# 02_POWER.net
KiCad netlist of a schematic drawn in Altium Designer
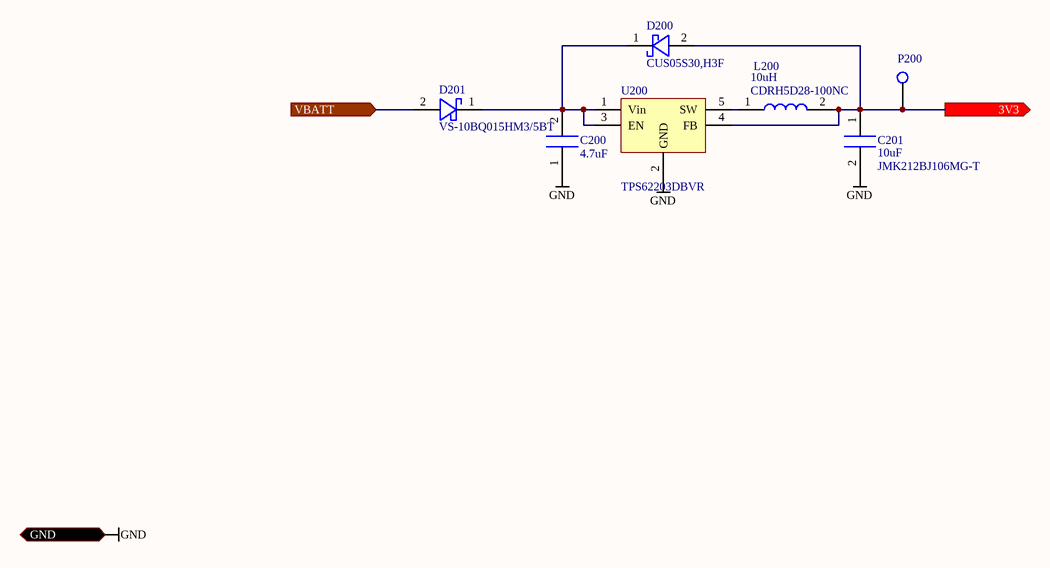
[diagram p0: 02_POWER.SchDoc]

(export (version "E")
  (design (tool "Eeschema 10.0.6"))
  (components
    (comp (ref "C200")
      (value "4.7uF")
      (footprint "CAP_0805")
      (description "CAP 4.7uF 10% 106 0805 X7R")
      (fields (field (name "TOLERANCE") "10%") (field (name "MANUFACTURER") "MURATA"))
      (libsource (lib "Capacitors") (part "4.7uF_10%_16V_0805_X7R_GRM21BR71C475KE51L"))
    )
    (comp (ref "C201")
      (value "10uF")
      (footprint "CAP_0805")
      (description "CAP 10uF 20% 6.3V 0805 X5R")
      (fields
        (field (name "TOLERANCE") "20%")
        (field (name "MANUFACTURER") "TAYIO YUDEN")
        (field (name "MANUFACTURER REFERENCE") "JMK212BJ106MG-T")
      )
      (libsource (lib "Capacitors") (part "10uF_20%_6.3V_0805_X5R_JMK212BJ106MG-T"))
    )
    (comp (ref "D200")
      (value "DIODE_30V_500mA_340mVf_CUS05S30,H3F")
      (footprint "SOD-323")
      (description "DIODE 30V 500mA 340mVf CUS05S30,H3F")
      (fields (field (name "MANUFACTURER") "TOSHIBA") (field (name "MANUFACTURER REFERENCE") "CUS05S30,H3F"))
      (libsource (lib "Semiconductor") (part "DIODE_30V_500mA_340mVf_CUS05S30,H3F"))
    )
    (comp (ref "D201")
      (value "DIODE_15V_1A_210mVf_VS-10BQ015HM3/5BT")
      (description "DIODE 15V 1A 210mVf VS-10BQ015HM3/5BT")
      (fields
        (field (name "MANUFACTURER") "VISHAY")
        (field (name "MANUFACTURER REFERENCE") "VS-10BQ015HM3/5BT")
      )
      (libsource (lib "Semiconductor") (part "DIODE_15V_1A_210mVf_VS-10BQ015HM3/5BT"))
    )
    (comp (ref "L200")
      (value "10uH")
      (footprint "CDRH5D28-100NC")
      (description "INDUCTOR 10uH 30% 1.3A CDRH5D28-100NC")
      (fields
        (field (name "TOLERANCE") "30%")
        (field (name "MANUFACTURER") "SUMIDA")
        (field (name "MANUFACTURER REFERENCE") "CDRH5D28-100NC")
      )
      (libsource (lib "Inductors") (part "10uH_30%_1.3A_CDRH5D28-100NC"))
    )
    (comp (ref "P200")
      (value "TEST_POINT_2mm")
      (footprint "TEST_POINT_2mm")
      (libsource (lib "Connectors") (part "TEST_POINT_2mm"))
    )
    (comp (ref "U200")
      (value "DCDC_6VIN_3.3VOUT_600mA_TPS62203DBVR")
      (footprint "SC-74A-5 SOT-23-5")
      (description "DCDC 2-5Vin 3.3Vout 1A 300mA TPS62203DBVR")
      (fields (field (name "MANUFACTURER") "TI") (field (name "MANUFACTURER REFERENCE") "TPS62203DBVR"))
      (libsource (lib "Semiconductor") (part "DCDC_5VIN_3.3VOUT_1A_TPS62203DBVR"))
    )
  )
  (nets
    (net (code "1") (name "/3V3") (class "Default")
      (node (ref "C201") (pin "1") (pinfunction "1_1") (pintype "passive"))
      (node (ref "D200") (pin "2") (pinfunction "2_2") (pintype "passive"))
      (node (ref "L200") (pin "2") (pinfunction "2_2") (pintype "passive"))
      (node (ref "P200") (pin "1") (pinfunction "1_1") (pintype "passive"))
      (node (ref "U200") (pin "4") (pinfunction "FB_4") (pintype "passive"))
    )
    (net (code "2") (name "/VBATT") (class "Default")
      (node (ref "D201") (pin "2") (pinfunction "2_2") (pintype "passive"))
    )
    (net (code "3") (name "GND") (class "Default")
      (node (ref "C200") (pin "1") (pinfunction "1_1") (pintype "passive"))
      (node (ref "C201") (pin "2") (pinfunction "2_2") (pintype "passive"))
      (node (ref "U200") (pin "2") (pinfunction "GND_2") (pintype "passive"))
    )
    (net (code "4") (name "Net-(U200-EN)") (class "Default")
      (node (ref "C200") (pin "2") (pinfunction "2_2") (pintype "passive"))
      (node (ref "D200") (pin "1") (pinfunction "1_1") (pintype "passive"))
      (node (ref "D201") (pin "1") (pinfunction "1_1") (pintype "passive"))
      (node (ref "U200") (pin "1") (pinfunction "Vin_1") (pintype "passive"))
      (node (ref "U200") (pin "3") (pinfunction "EN_3") (pintype "passive"))
    )
    (net (code "5") (name "Net-(U200-SW)") (class "Default")
      (node (ref "L200") (pin "1") (pinfunction "1_1") (pintype "passive"))
      (node (ref "U200") (pin "5") (pinfunction "SW_5") (pintype "passive"))
    )
  )
)
